# final_pcb.net
KiCad netlist of a schematic drawn in EAGLE
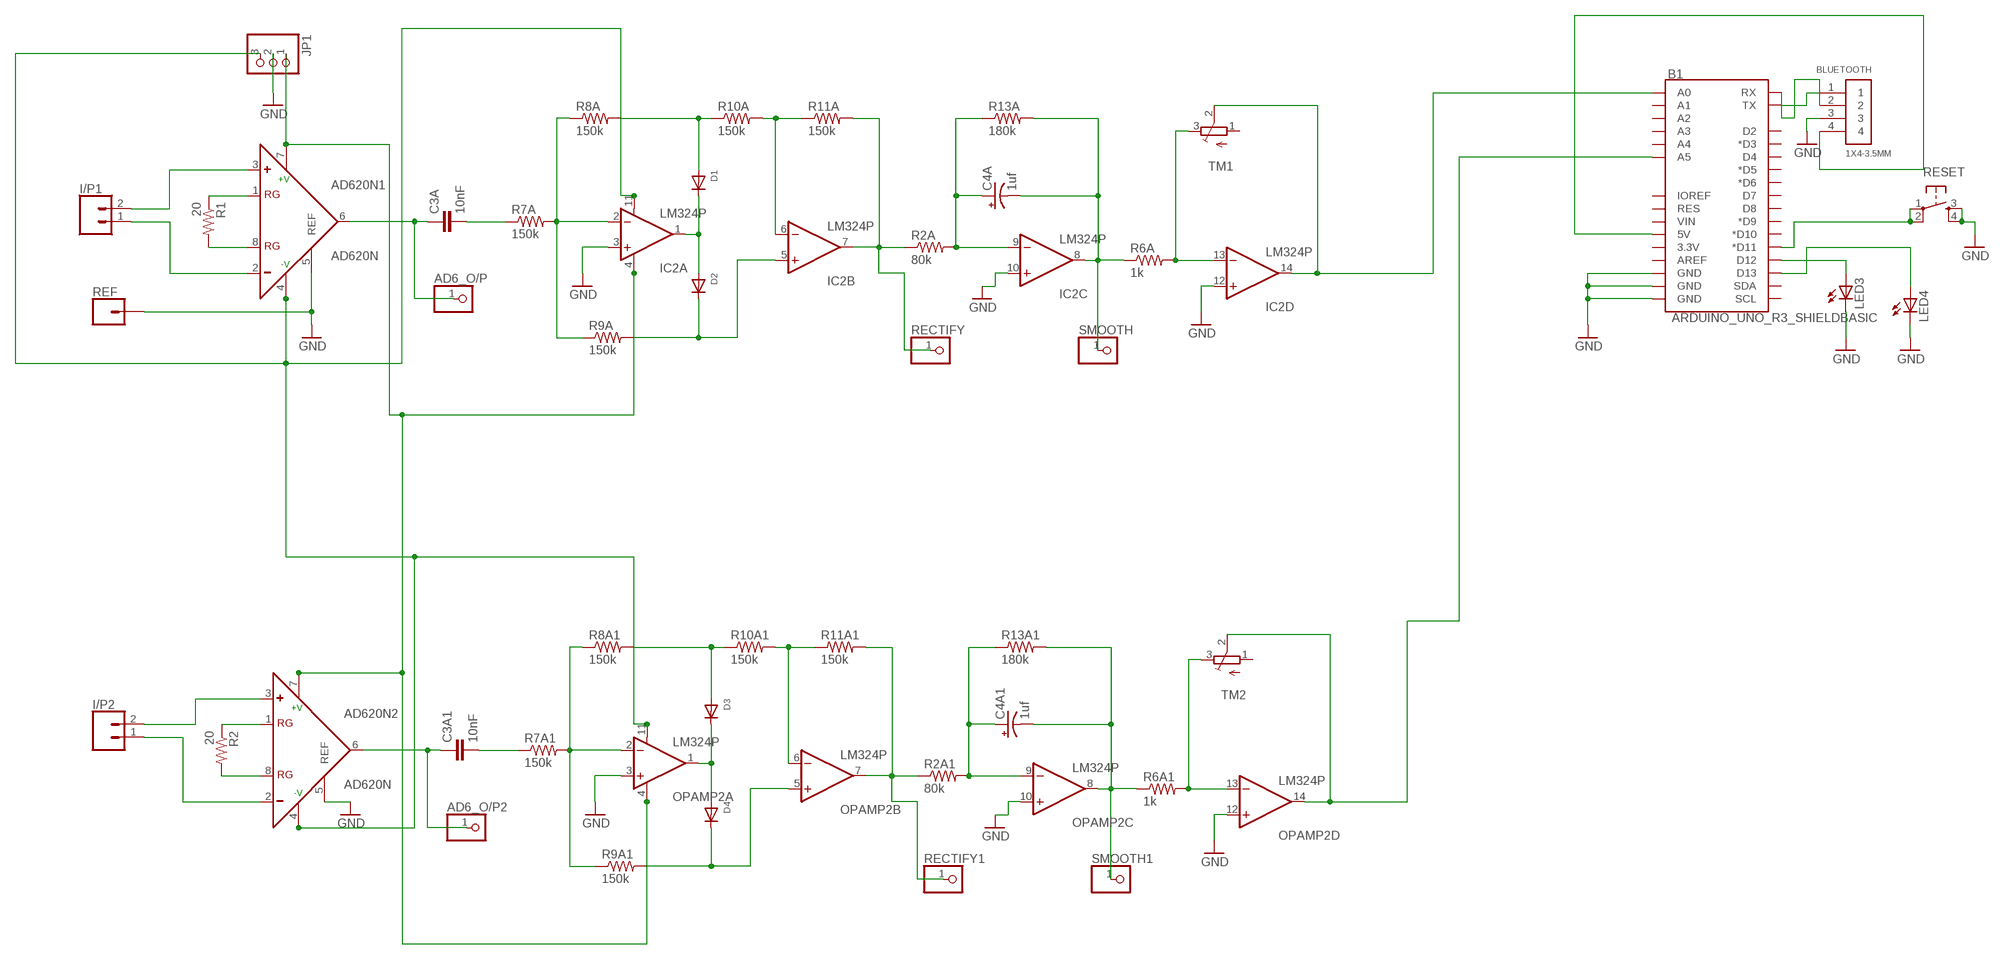
[diagram p0: schematic, sheet 1]

(export (version "E")
  (design (tool "Eeschema 10.0.6"))
  (components
    (comp (ref "AD6_O/P")
      (value "PINHD-1X1")
      (footprint "eagle-import:1X01")
      (libsource (lib "eagle-import") (part "PINHD-1X1"))
    )
    (comp (ref "AD6_O/P2")
      (value "PINHD-1X1")
      (footprint "eagle-import:1X01")
      (libsource (lib "eagle-import") (part "PINHD-1X1"))
    )
    (comp (ref "AD620N1")
      (value "AD620N")
      (footprint "eagle-import:DIL08")
      (fields (field (name "MF") "ALTERA CORPORATION") (field (name "MPN") "AD620AN"))
      (libsource (lib "eagle-import") (part "AD620N"))
    )
    (comp (ref "AD620N2")
      (value "AD620N")
      (footprint "eagle-import:DIL08")
      (fields (field (name "MF") "ALTERA CORPORATION") (field (name "MPN") "AD620AN"))
      (libsource (lib "eagle-import") (part "AD620N"))
    )
    (comp (ref "B1")
      (value "ARDUINO_UNO_R3_SHIELDBASIC")
      (footprint "eagle-import:UNO_R3_SHIELD")
      (libsource (lib "eagle-import") (part "ARDUINO_UNO_R3_SHIELDBASIC"))
    )
    (comp (ref "BLUETOOTH")
      (value "1X4-3.5MM")
      (footprint "eagle-import:1X04-3.5MM")
      (libsource (lib "eagle-import") (part "1X4-3.5MM"))
    )
    (comp (ref "C3A")
      (value "10nF")
      (footprint "eagle-import:CAP-PTH-10MM")
      (libsource (lib "eagle-import") (part "10NF-PTH-10MM-10000V-1-%"))
    )
    (comp (ref "C3A1")
      (value "10nF")
      (footprint "eagle-import:CAP-PTH-10MM")
      (libsource (lib "eagle-import") (part "10NF-PTH-10MM-10000V-1-%"))
    )
    (comp (ref "C4A")
      (value "1uf")
      (footprint "eagle-import:CPOL-RADIAL-5MM-10MM-KIT")
      (libsource (lib "eagle-import") (part "1000UF-RADIAL-5MM-35V-20%-KIT"))
    )
    (comp (ref "C4A1")
      (value "1uf")
      (footprint "eagle-import:CPOL-RADIAL-5MM-10MM-KIT")
      (libsource (lib "eagle-import") (part "1000UF-RADIAL-5MM-35V-20%-KIT"))
    )
    (comp (ref "D1")
      (value "DIODEDO-1N4148")
      (footprint "eagle-import:DO-1N4148")
      (libsource (lib "eagle-import") (part "DIODEDO-1N4148"))
    )
    (comp (ref "D2")
      (value "DIODEDO-1N4148")
      (footprint "eagle-import:DO-1N4148")
      (libsource (lib "eagle-import") (part "DIODEDO-1N4148"))
    )
    (comp (ref "D3")
      (value "DIODEDO-1N4148")
      (footprint "eagle-import:DO-1N4148")
      (libsource (lib "eagle-import") (part "DIODEDO-1N4148"))
    )
    (comp (ref "D4")
      (value "DIODEDO-1N4148")
      (footprint "eagle-import:DO-1N4148")
      (libsource (lib "eagle-import") (part "DIODEDO-1N4148"))
    )
    (comp (ref "I/P1")
      (value "CONN_02")
      (footprint "eagle-import:1X02")
      (libsource (lib "eagle-import") (part "CONN_02"))
    )
    (comp (ref "I/P2")
      (value "CONN_02")
      (footprint "eagle-import:1X02")
      (libsource (lib "eagle-import") (part "CONN_02"))
    )
    (comp (ref "IC2")
      (value "LM324P")
      (footprint "eagle-import:DIL14")
      (libsource (lib "eagle-import") (part "LM324P"))
    )
    (comp (ref "JP1")
      (value "PINHD-1X3")
      (footprint "eagle-import:1X03")
      (libsource (lib "eagle-import") (part "PINHD-1X3"))
    )
    (comp (ref "LED3")
      (value "LED5MM")
      (footprint "eagle-import:LED5MM")
      (libsource (lib "eagle-import") (part "LED5MM"))
    )
    (comp (ref "LED4")
      (value "LED5MM")
      (footprint "eagle-import:LED5MM")
      (libsource (lib "eagle-import") (part "LED5MM"))
    )
    (comp (ref "OPAMP2")
      (value "LM324P")
      (footprint "eagle-import:DIL14")
      (libsource (lib "eagle-import") (part "LM324P"))
    )
    (comp (ref "R1")
      (value "20")
      (footprint "eagle-import:0207_9")
      (libsource (lib "eagle-import") (part "R-US_0207/9"))
    )
    (comp (ref "R2")
      (value "20")
      (footprint "eagle-import:0207_9")
      (libsource (lib "eagle-import") (part "R-US_0207/9"))
    )
    (comp (ref "R2A")
      (value "80k")
      (footprint "eagle-import:0207_9")
      (libsource (lib "eagle-import") (part "R-US_0207/9"))
    )
    (comp (ref "R2A1")
      (value "80k")
      (footprint "eagle-import:0207_9")
      (libsource (lib "eagle-import") (part "R-US_0207/9"))
    )
    (comp (ref "R6A")
      (value "1k")
      (footprint "eagle-import:0207_9")
      (libsource (lib "eagle-import") (part "R-US_0207/9"))
    )
    (comp (ref "R6A1")
      (value "1k")
      (footprint "eagle-import:0207_9")
      (libsource (lib "eagle-import") (part "R-US_0207/9"))
    )
    (comp (ref "R7A")
      (value "150k")
      (footprint "eagle-import:0207_9")
      (libsource (lib "eagle-import") (part "R-US_0207/9"))
    )
    (comp (ref "R7A1")
      (value "150k")
      (footprint "eagle-import:0207_9")
      (libsource (lib "eagle-import") (part "R-US_0207/9"))
    )
    (comp (ref "R8A")
      (value "150k")
      (footprint "eagle-import:0207_9")
      (libsource (lib "eagle-import") (part "R-US_0207/9"))
    )
    (comp (ref "R8A1")
      (value "150k")
      (footprint "eagle-import:0207_9")
      (libsource (lib "eagle-import") (part "R-US_0207/9"))
    )
    (comp (ref "R9A")
      (value "150k")
      (footprint "eagle-import:0207_9")
      (libsource (lib "eagle-import") (part "R-US_0207/9"))
    )
    (comp (ref "R9A1")
      (value "150k")
      (footprint "eagle-import:0207_9")
      (libsource (lib "eagle-import") (part "R-US_0207/9"))
    )
    (comp (ref "R10A")
      (value "150k")
      (footprint "eagle-import:0207_9")
      (libsource (lib "eagle-import") (part "R-US_0207/9"))
    )
    (comp (ref "R10A1")
      (value "150k")
      (footprint "eagle-import:0207_9")
      (libsource (lib "eagle-import") (part "R-US_0207/9"))
    )
    (comp (ref "R11A")
      (value "150k")
      (footprint "eagle-import:0207_9")
      (libsource (lib "eagle-import") (part "R-US_0207/9"))
    )
    (comp (ref "R11A1")
      (value "150k")
      (footprint "eagle-import:0207_9")
      (libsource (lib "eagle-import") (part "R-US_0207/9"))
    )
    (comp (ref "R13A")
      (value "180k")
      (footprint "eagle-import:0207_9")
      (libsource (lib "eagle-import") (part "R-US_0207/9"))
    )
    (comp (ref "R13A1")
      (value "180k")
      (footprint "eagle-import:0207_9")
      (libsource (lib "eagle-import") (part "R-US_0207/9"))
    )
    (comp (ref "RECTIFY")
      (value "PINHD-1X1")
      (footprint "eagle-import:1X01")
      (libsource (lib "eagle-import") (part "PINHD-1X1"))
    )
    (comp (ref "RECTIFY1")
      (value "PINHD-1X1")
      (footprint "eagle-import:1X01")
      (libsource (lib "eagle-import") (part "PINHD-1X1"))
    )
    (comp (ref "REF")
      (value "CONN_01")
      (footprint "eagle-import:1X01")
      (libsource (lib "eagle-import") (part "CONN_01"))
    )
    (comp (ref "RESET")
      (value "TAC_SWITCHPTH")
      (footprint "eagle-import:TACTILE-PTH")
      (libsource (lib "eagle-import") (part "TAC_SWITCHPTH"))
    )
    (comp (ref "SMOOTH")
      (value "PINHD-1X1")
      (footprint "eagle-import:1X01")
      (libsource (lib "eagle-import") (part "PINHD-1X1"))
    )
    (comp (ref "SMOOTH1")
      (value "PINHD-1X1")
      (footprint "eagle-import:1X01")
      (libsource (lib "eagle-import") (part "PINHD-1X1"))
    )
    (comp (ref "TM1")
      (value "TRIMPOT3386")
      (footprint "eagle-import:TRIM-3386")
      (libsource (lib "eagle-import") (part "TRIMPOT3386"))
    )
    (comp (ref "TM2")
      (value "TRIMPOT3386")
      (footprint "eagle-import:TRIM-3386")
      (libsource (lib "eagle-import") (part "TRIMPOT3386"))
    )
  )
  (nets
    (net (code "1") (name "GND") (class "Default")
      (node (ref "AD620N1") (pin "5") (pinfunction "REF_5") (pintype "passive"))
      (node (ref "AD620N2") (pin "5") (pinfunction "REF_5") (pintype "passive"))
      (node (ref "B1") (pin "GND@0") (pinfunction "GND_GND@0") (pintype "bidirectional"))
      (node (ref "B1") (pin "GND@1") (pinfunction "GND_GND@1") (pintype "bidirectional"))
      (node (ref "B1") (pin "GND@2") (pinfunction "GND_GND@2") (pintype "bidirectional"))
      (node (ref "BLUETOOTH") (pin "3") (pinfunction "3_3") (pintype "bidirectional"))
      (node (ref "IC2") (pin "10") (pinfunction "+IN_10") (pintype "input"))
      (node (ref "IC2") (pin "12") (pinfunction "+IN_12") (pintype "input"))
      (node (ref "IC2") (pin "3") (pinfunction "+IN_3") (pintype "input"))
      (node (ref "JP1") (pin "2") (pinfunction "2_2") (pintype "passive"))
      (node (ref "LED3") (pin "K") (pinfunction "C_K") (pintype "passive"))
      (node (ref "LED4") (pin "K") (pinfunction "C_K") (pintype "passive"))
      (node (ref "OPAMP2") (pin "10") (pinfunction "+IN_10") (pintype "input"))
      (node (ref "OPAMP2") (pin "12") (pinfunction "+IN_12") (pintype "input"))
      (node (ref "OPAMP2") (pin "3") (pinfunction "+IN_3") (pintype "input"))
      (node (ref "REF") (pin "1") (pinfunction "1_1") (pintype "passive"))
      (node (ref "RESET") (pin "3") (pinfunction "3_3") (pintype "passive"))
      (node (ref "RESET") (pin "4") (pinfunction "4_4") (pintype "passive"))
    )
    (net (code "2") (name "Net-(AD620N1-+)") (class "Default")
      (node (ref "AD620N1") (pin "3") (pinfunction "+_3") (pintype "input"))
      (node (ref "I/P1") (pin "2") (pinfunction "2_2") (pintype "passive"))
    )
    (net (code "3") (name "Net-(AD620N1-+V)") (class "Default")
      (node (ref "AD620N1") (pin "7") (pinfunction "+V_7") (pintype "power_in"))
      (node (ref "AD620N2") (pin "7") (pinfunction "+V_7") (pintype "power_in"))
      (node (ref "IC2") (pin "4") (pinfunction "V+_4") (pintype "power_in"))
      (node (ref "JP1") (pin "1") (pinfunction "1_1") (pintype "passive"))
      (node (ref "OPAMP2") (pin "4") (pinfunction "V+_4") (pintype "power_in"))
    )
    (net (code "4") (name "Net-(AD620N1--)") (class "Default")
      (node (ref "AD620N1") (pin "2") (pinfunction "-_2") (pintype "input"))
      (node (ref "I/P1") (pin "1") (pinfunction "1_1") (pintype "passive"))
    )
    (net (code "5") (name "Net-(AD620N1--V)") (class "Default")
      (node (ref "AD620N1") (pin "4") (pinfunction "-V_4") (pintype "power_in"))
      (node (ref "AD620N2") (pin "4") (pinfunction "-V_4") (pintype "power_in"))
      (node (ref "IC2") (pin "11") (pinfunction "V-_11") (pintype "power_in"))
      (node (ref "JP1") (pin "3") (pinfunction "3_3") (pintype "passive"))
      (node (ref "OPAMP2") (pin "11") (pinfunction "V-_11") (pintype "power_in"))
    )
    (net (code "6") (name "Net-(AD620N1-OUT)") (class "Default")
      (node (ref "AD620N1") (pin "6") (pinfunction "OUT_6") (pintype "output"))
      (node (ref "AD6_O/P") (pin "1") (pinfunction "1_1") (pintype "passive"))
      (node (ref "C3A") (pin "1") (pinfunction "1_1") (pintype "passive"))
    )
    (net (code "7") (name "Net-(AD620N1-RG-Pad1)") (class "Default")
      (node (ref "AD620N1") (pin "1") (pinfunction "RG_1") (pintype "passive"))
      (node (ref "R1") (pin "1") (pinfunction "1_1") (pintype "passive"))
    )
    (net (code "8") (name "Net-(AD620N1-RG-Pad8)") (class "Default")
      (node (ref "AD620N1") (pin "8") (pinfunction "RG_8") (pintype "passive"))
      (node (ref "R1") (pin "2") (pinfunction "2_2") (pintype "passive"))
    )
    (net (code "9") (name "Net-(AD620N2-+)") (class "Default")
      (node (ref "AD620N2") (pin "3") (pinfunction "+_3") (pintype "input"))
      (node (ref "I/P2") (pin "2") (pinfunction "2_2") (pintype "passive"))
    )
    (net (code "10") (name "Net-(AD620N2--)") (class "Default")
      (node (ref "AD620N2") (pin "2") (pinfunction "-_2") (pintype "input"))
      (node (ref "I/P2") (pin "1") (pinfunction "1_1") (pintype "passive"))
    )
    (net (code "11") (name "Net-(AD620N2-OUT)") (class "Default")
      (node (ref "AD620N2") (pin "6") (pinfunction "OUT_6") (pintype "output"))
      (node (ref "AD6_O/P2") (pin "1") (pinfunction "1_1") (pintype "passive"))
      (node (ref "C3A1") (pin "1") (pinfunction "1_1") (pintype "passive"))
    )
    (net (code "12") (name "Net-(AD620N2-RG-Pad1)") (class "Default")
      (node (ref "AD620N2") (pin "1") (pinfunction "RG_1") (pintype "passive"))
      (node (ref "R2") (pin "1") (pinfunction "1_1") (pintype "passive"))
    )
    (net (code "13") (name "Net-(AD620N2-RG-Pad8)") (class "Default")
      (node (ref "AD620N2") (pin "8") (pinfunction "RG_8") (pintype "passive"))
      (node (ref "R2") (pin "2") (pinfunction "2_2") (pintype "passive"))
    )
    (net (code "14") (name "Net-(B1-*D11)") (class "Default")
      (node (ref "B1") (pin "D11") (pinfunction "*D11_D11") (pintype "bidirectional"))
      (node (ref "RESET") (pin "1") (pinfunction "1_1") (pintype "passive"))
      (node (ref "RESET") (pin "2") (pinfunction "2_2") (pintype "passive"))
    )
    (net (code "15") (name "Net-(B1-Pad5V)") (class "Default")
      (node (ref "B1") (pin "5V") (pinfunction "5V_5V") (pintype "bidirectional"))
      (node (ref "BLUETOOTH") (pin "4") (pinfunction "4_4") (pintype "bidirectional"))
    )
    (net (code "16") (name "Net-(B1-PadD12)") (class "Default")
      (node (ref "B1") (pin "D12") (pinfunction "D12_D12") (pintype "bidirectional"))
      (node (ref "LED3") (pin "A") (pinfunction "A_A") (pintype "passive"))
    )
    (net (code "17") (name "Net-(B1-PadD13)") (class "Default")
      (node (ref "B1") (pin "D13") (pinfunction "D13_D13") (pintype "bidirectional"))
      (node (ref "LED4") (pin "A") (pinfunction "A_A") (pintype "passive"))
    )
    (net (code "18") (name "Net-(B1-PadRX)") (class "Default")
      (node (ref "B1") (pin "RX") (pinfunction "RX_RX") (pintype "bidirectional"))
      (node (ref "BLUETOOTH") (pin "2") (pinfunction "2_2") (pintype "bidirectional"))
    )
    (net (code "19") (name "Net-(B1-PadTX)") (class "Default")
      (node (ref "B1") (pin "TX") (pinfunction "TX_TX") (pintype "bidirectional"))
      (node (ref "BLUETOOTH") (pin "1") (pinfunction "1_1") (pintype "bidirectional"))
    )
    (net (code "20") (name "Net-(C3A-Pad2)") (class "Default")
      (node (ref "C3A") (pin "2") (pinfunction "2_2") (pintype "passive"))
      (node (ref "R7A") (pin "1") (pinfunction "1_1") (pintype "passive"))
    )
    (net (code "21") (name "Net-(C3A1-Pad2)") (class "Default")
      (node (ref "C3A1") (pin "2") (pinfunction "2_2") (pintype "passive"))
      (node (ref "R7A1") (pin "1") (pinfunction "1_1") (pintype "passive"))
    )
    (net (code "22") (name "Net-(D1-PadA)") (class "Default")
      (node (ref "D1") (pin "A") (pinfunction "A_A") (pintype "passive"))
      (node (ref "R10A") (pin "1") (pinfunction "1_1") (pintype "passive"))
      (node (ref "R8A") (pin "2") (pinfunction "2_2") (pintype "passive"))
    )
    (net (code "23") (name "Net-(D3-PadA)") (class "Default")
      (node (ref "D3") (pin "A") (pinfunction "A_A") (pintype "passive"))
      (node (ref "R10A1") (pin "1") (pinfunction "1_1") (pintype "passive"))
      (node (ref "R8A1") (pin "2") (pinfunction "2_2") (pintype "passive"))
    )
    (net (code "24") (name "Net-(IC2A--IN)") (class "Default")
      (node (ref "IC2") (pin "2") (pinfunction "-IN_2") (pintype "input"))
      (node (ref "R7A") (pin "2") (pinfunction "2_2") (pintype "passive"))
      (node (ref "R8A") (pin "1") (pinfunction "1_1") (pintype "passive"))
      (node (ref "R9A") (pin "1") (pinfunction "1_1") (pintype "passive"))
    )
    (net (code "25") (name "Net-(IC2A-OUT)") (class "Default")
      (node (ref "D1") (pin "C") (pinfunction "C_C") (pintype "passive"))
      (node (ref "D2") (pin "A") (pinfunction "A_A") (pintype "passive"))
      (node (ref "IC2") (pin "1") (pinfunction "OUT_1") (pintype "output"))
    )
    (net (code "26") (name "Net-(IC2B-+IN)") (class "Default")
      (node (ref "D2") (pin "C") (pinfunction "C_C") (pintype "passive"))
      (node (ref "IC2") (pin "5") (pinfunction "+IN_5") (pintype "input"))
      (node (ref "R9A") (pin "2") (pinfunction "2_2") (pintype "passive"))
    )
    (net (code "27") (name "Net-(IC2B--IN)") (class "Default")
      (node (ref "IC2") (pin "6") (pinfunction "-IN_6") (pintype "input"))
      (node (ref "R10A") (pin "2") (pinfunction "2_2") (pintype "passive"))
      (node (ref "R11A") (pin "1") (pinfunction "1_1") (pintype "passive"))
    )
    (net (code "28") (name "Net-(IC2B-OUT)") (class "Default")
      (node (ref "IC2") (pin "7") (pinfunction "OUT_7") (pintype "output"))
      (node (ref "R11A") (pin "2") (pinfunction "2_2") (pintype "passive"))
      (node (ref "R2A") (pin "1") (pinfunction "1_1") (pintype "passive"))
      (node (ref "RECTIFY") (pin "1") (pinfunction "1_1") (pintype "passive"))
    )
    (net (code "29") (name "Net-(IC2C--IN)") (class "Default")
      (node (ref "C4A") (pin "+") (pinfunction "+_+") (pintype "passive"))
      (node (ref "IC2") (pin "9") (pinfunction "-IN_9") (pintype "input"))
      (node (ref "R13A") (pin "1") (pinfunction "1_1") (pintype "passive"))
      (node (ref "R2A") (pin "2") (pinfunction "2_2") (pintype "passive"))
    )
    (net (code "30") (name "Net-(IC2C-OUT)") (class "Default")
      (node (ref "C4A") (pin "-") (pinfunction "-_-") (pintype "passive"))
      (node (ref "IC2") (pin "8") (pinfunction "OUT_8") (pintype "output"))
      (node (ref "R13A") (pin "2") (pinfunction "2_2") (pintype "passive"))
      (node (ref "R6A") (pin "1") (pinfunction "1_1") (pintype "passive"))
      (node (ref "SMOOTH") (pin "1") (pinfunction "1_1") (pintype "passive"))
    )
    (net (code "31") (name "Net-(IC2D--IN)") (class "Default")
      (node (ref "IC2") (pin "13") (pinfunction "-IN_13") (pintype "input"))
      (node (ref "R6A") (pin "2") (pinfunction "2_2") (pintype "passive"))
      (node (ref "TM1") (pin "3") (pinfunction "E_3") (pintype "passive"))
    )
    (net (code "32") (name "Net-(IC2D-OUT)") (class "Default")
      (node (ref "B1") (pin "A0") (pinfunction "A0_A0") (pintype "bidirectional"))
      (node (ref "IC2") (pin "14") (pinfunction "OUT_14") (pintype "output"))
      (node (ref "TM1") (pin "2") (pinfunction "S_2") (pintype "passive"))
    )
    (net (code "33") (name "Net-(OPAMP2A--IN)") (class "Default")
      (node (ref "OPAMP2") (pin "2") (pinfunction "-IN_2") (pintype "input"))
      (node (ref "R7A1") (pin "2") (pinfunction "2_2") (pintype "passive"))
      (node (ref "R8A1") (pin "1") (pinfunction "1_1") (pintype "passive"))
      (node (ref "R9A1") (pin "1") (pinfunction "1_1") (pintype "passive"))
    )
    (net (code "34") (name "Net-(OPAMP2A-OUT)") (class "Default")
      (node (ref "D3") (pin "C") (pinfunction "C_C") (pintype "passive"))
      (node (ref "D4") (pin "A") (pinfunction "A_A") (pintype "passive"))
      (node (ref "OPAMP2") (pin "1") (pinfunction "OUT_1") (pintype "output"))
    )
    (net (code "35") (name "Net-(OPAMP2B-+IN)") (class "Default")
      (node (ref "D4") (pin "C") (pinfunction "C_C") (pintype "passive"))
      (node (ref "OPAMP2") (pin "5") (pinfunction "+IN_5") (pintype "input"))
      (node (ref "R9A1") (pin "2") (pinfunction "2_2") (pintype "passive"))
    )
    (net (code "36") (name "Net-(OPAMP2B--IN)") (class "Default")
      (node (ref "OPAMP2") (pin "6") (pinfunction "-IN_6") (pintype "input"))
      (node (ref "R10A1") (pin "2") (pinfunction "2_2") (pintype "passive"))
      (node (ref "R11A1") (pin "1") (pinfunction "1_1") (pintype "passive"))
    )
    (net (code "37") (name "Net-(OPAMP2B-OUT)") (class "Default")
      (node (ref "OPAMP2") (pin "7") (pinfunction "OUT_7") (pintype "output"))
      (node (ref "R11A1") (pin "2") (pinfunction "2_2") (pintype "passive"))
      (node (ref "R2A1") (pin "1") (pinfunction "1_1") (pintype "passive"))
      (node (ref "RECTIFY1") (pin "1") (pinfunction "1_1") (pintype "passive"))
    )
    (net (code "38") (name "Net-(OPAMP2C--IN)") (class "Default")
      (node (ref "C4A1") (pin "+") (pinfunction "+_+") (pintype "passive"))
      (node (ref "OPAMP2") (pin "9") (pinfunction "-IN_9") (pintype "input"))
      (node (ref "R13A1") (pin "1") (pinfunction "1_1") (pintype "passive"))
      (node (ref "R2A1") (pin "2") (pinfunction "2_2") (pintype "passive"))
    )
    (net (code "39") (name "Net-(OPAMP2C-OUT)") (class "Default")
      (node (ref "C4A1") (pin "-") (pinfunction "-_-") (pintype "passive"))
      (node (ref "OPAMP2") (pin "8") (pinfunction "OUT_8") (pintype "output"))
      (node (ref "R13A1") (pin "2") (pinfunction "2_2") (pintype "passive"))
      (node (ref "R6A1") (pin "1") (pinfunction "1_1") (pintype "passive"))
      (node (ref "SMOOTH1") (pin "1") (pinfunction "1_1") (pintype "passive"))
    )
    (net (code "40") (name "Net-(OPAMP2D--IN)") (class "Default")
      (node (ref "OPAMP2") (pin "13") (pinfunction "-IN_13") (pintype "input"))
      (node (ref "R6A1") (pin "2") (pinfunction "2_2") (pintype "passive"))
      (node (ref "TM2") (pin "3") (pinfunction "E_3") (pintype "passive"))
    )
    (net (code "41") (name "Net-(OPAMP2D-OUT)") (class "Default")
      (node (ref "B1") (pin "A5") (pinfunction "A5_A5") (pintype "bidirectional"))
      (node (ref "OPAMP2") (pin "14") (pinfunction "OUT_14") (pintype "output"))
      (node (ref "TM2") (pin "2") (pinfunction "S_2") (pintype "passive"))
    )
    (net (code "42") (name "unconnected-(B1-*D3-PadD3)") (class "Default")
      (node (ref "B1") (pin "D3") (pinfunction "*D3_D3") (pintype "bidirectional"))
    )
    (net (code "43") (name "unconnected-(B1-*D5-PadD5)") (class "Default")
      (node (ref "B1") (pin "D5") (pinfunction "*D5_D5") (pintype "bidirectional"))
    )
    (net (code "44") (name "unconnected-(B1-*D6-PadD6)") (class "Default")
      (node (ref "B1") (pin "D6") (pinfunction "*D6_D6") (pintype "bidirectional"))
    )
    (net (code "45") (name "unconnected-(B1-*D9-PadD9)") (class "Default")
      (node (ref "B1") (pin "D9") (pinfunction "*D9_D9") (pintype "bidirectional"))
    )
    (net (code "46") (name "unconnected-(B1-*D10-PadD10)") (class "Default")
      (node (ref "B1") (pin "D10") (pinfunction "*D10_D10") (pintype "bidirectional"))
    )
    (net (code "47") (name "unconnected-(B1-Pad3.3V)") (class "Default")
      (node (ref "B1") (pin "3.3V") (pinfunction "3.3V_3.3V") (pintype "bidirectional"))
    )
    (net (code "48") (name "unconnected-(B1-PadA1)") (class "Default")
      (node (ref "B1") (pin "A1") (pinfunction "A1_A1") (pintype "bidirectional"))
    )
    (net (code "49") (name "unconnected-(B1-PadA2)") (class "Default")
      (node (ref "B1") (pin "A2") (pinfunction "A2_A2") (pintype "bidirectional"))
    )
    (net (code "50") (name "unconnected-(B1-PadA3)") (class "Default")
      (node (ref "B1") (pin "A3") (pinfunction "A3_A3") (pintype "bidirectional"))
    )
    (net (code "51") (name "unconnected-(B1-PadA4)") (class "Default")
      (node (ref "B1") (pin "A4") (pinfunction "A4_A4") (pintype "bidirectional"))
    )
    (net (code "52") (name "unconnected-(B1-PadAREF)") (class "Default")
      (node (ref "B1") (pin "AREF") (pinfunction "AREF_AREF") (pintype "bidirectional"))
    )
    (net (code "53") (name "unconnected-(B1-PadD2)") (class "Default")
      (node (ref "B1") (pin "D2") (pinfunction "D2_D2") (pintype "bidirectional"))
    )
    (net (code "54") (name "unconnected-(B1-PadD4)") (class "Default")
      (node (ref "B1") (pin "D4") (pinfunction "D4_D4") (pintype "bidirectional"))
    )
    (net (code "55") (name "unconnected-(B1-PadD7)") (class "Default")
      (node (ref "B1") (pin "D7") (pinfunction "D7_D7") (pintype "bidirectional"))
    )
    (net (code "56") (name "unconnected-(B1-PadD8)") (class "Default")
      (node (ref "B1") (pin "D8") (pinfunction "D8_D8") (pintype "bidirectional"))
    )
    (net (code "57") (name "unconnected-(B1-PadIOREF)") (class "Default")
      (node (ref "B1") (pin "IOREF") (pinfunction "IOREF_IOREF") (pintype "bidirectional"))
    )
    (net (code "58") (name "unconnected-(B1-PadRES)") (class "Default")
      (node (ref "B1") (pin "RES") (pinfunction "RES_RES") (pintype "bidirectional"))
    )
    (net (code "59") (name "unconnected-(B1-PadSCL)") (class "Default")
      (node (ref "B1") (pin "SCL") (pinfunction "SCL_SCL") (pintype "bidirectional"))
    )
    (net (code "60") (name "unconnected-(B1-PadSDA)") (class "Default")
      (node (ref "B1") (pin "SDA") (pinfunction "SDA_SDA") (pintype "bidirectional"))
    )
    (net (code "61") (name "unconnected-(B1-PadVIN)") (class "Default")
      (node (ref "B1") (pin "VIN") (pinfunction "VIN_VIN") (pintype "bidirectional"))
    )
    (net (code "62") (name "unconnected-(TM1-A-Pad1)") (class "Default")
      (node (ref "TM1") (pin "1") (pinfunction "A_1") (pintype "passive"))
    )
    (net (code "63") (name "unconnected-(TM2-A-Pad1)") (class "Default")
      (node (ref "TM2") (pin "1") (pinfunction "A_1") (pintype "passive"))
    )
  )
)
